# sensors_Layer_final.net
KiCad netlist of a schematic drawn in EAGLE
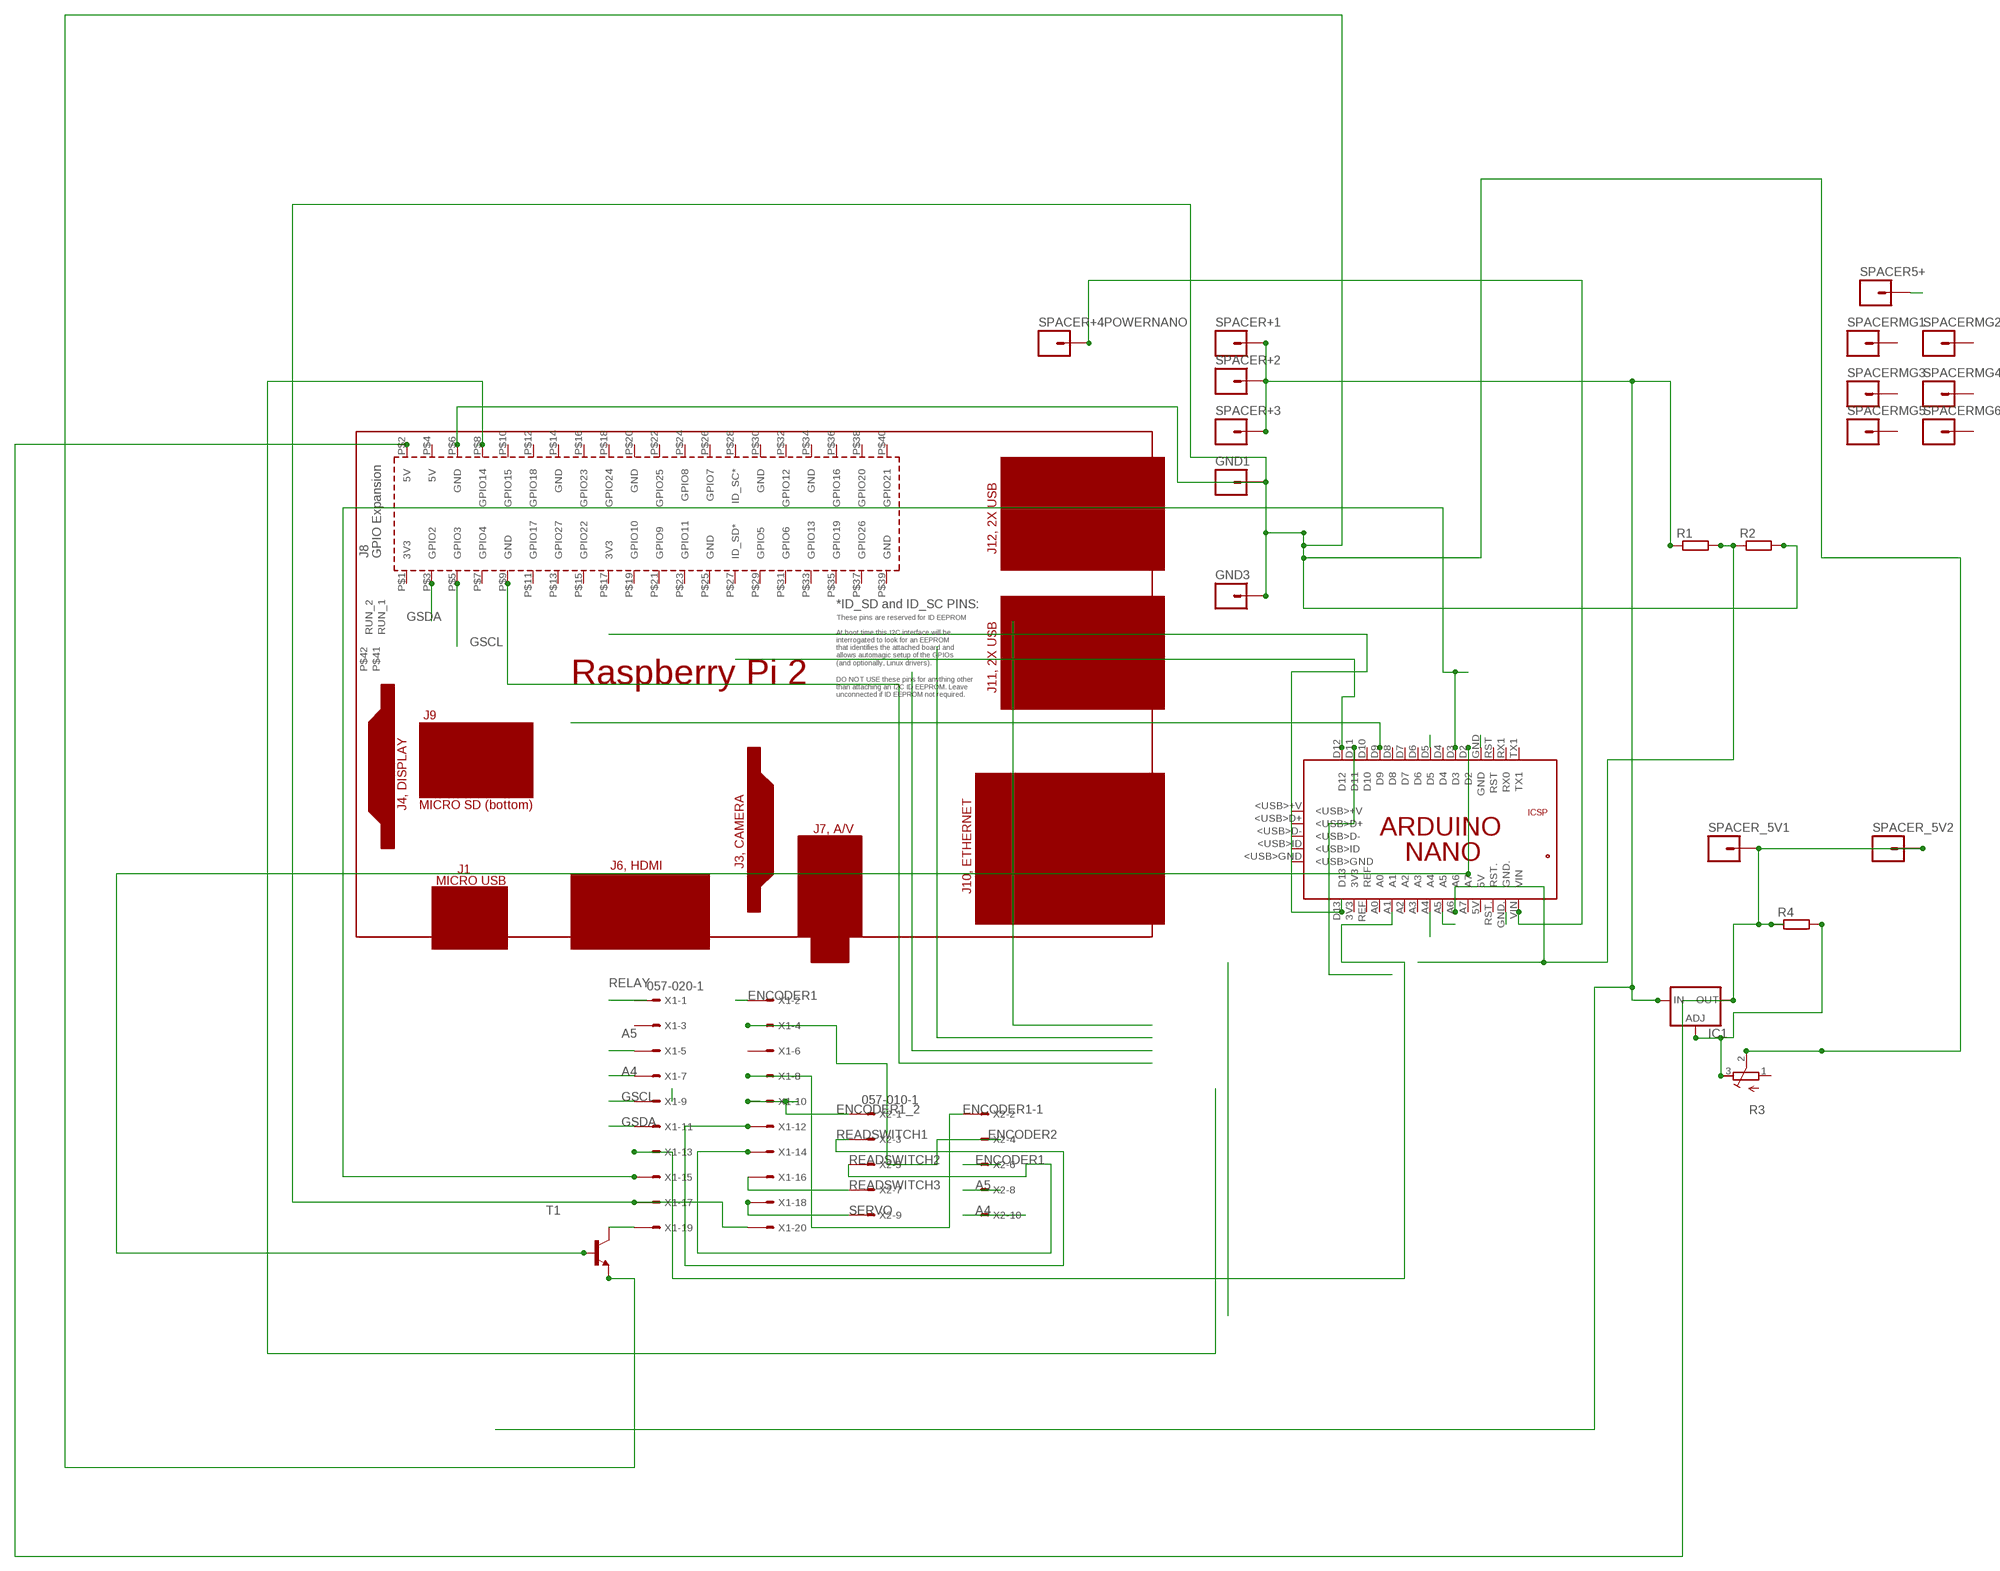
[diagram p0: schematic, sheet 1]

(export (version "E")
  (design (tool "Eeschema 10.0.6"))
  (components
    (comp (ref "GND1")
      (value "M01PTH_2MM")
      (footprint "eagle-import:1X01_2MM")
      (libsource (lib "eagle-import") (part "M01PTH_2MM"))
    )
    (comp (ref "GND3")
      (value "M01PTH_2MM")
      (footprint "eagle-import:1X01_2MM")
      (libsource (lib "eagle-import") (part "M01PTH_2MM"))
    )
    (comp (ref "IC1")
      (value "LM138-TO3")
      (footprint "eagle-import:TO3-K02")
      (libsource (lib "eagle-import") (part "LM138-TO3"))
    )
    (comp (ref "PCB1")
      (value "RPI2")
      (footprint "eagle-import:RPI2")
      (libsource (lib "eagle-import") (part "RPI2"))
    )
    (comp (ref "PCB2")
      (value "ARDUINO_NANO")
      (footprint "eagle-import:ARDUINO_NANO")
      (libsource (lib "eagle-import") (part "ARDUINO_NANO"))
    )
    (comp (ref "R1")
      (value "R-EU_0207/10")
      (footprint "eagle-import:0207_10")
      (libsource (lib "eagle-import") (part "R-EU_0207/10"))
    )
    (comp (ref "R2")
      (value "R-EU_0207/10")
      (footprint "eagle-import:0207_10")
      (libsource (lib "eagle-import") (part "R-EU_0207/10"))
    )
    (comp (ref "R3")
      (value "R-TRIMM64W")
      (footprint "eagle-import:RTRIM64W")
      (libsource (lib "eagle-import") (part "R-TRIMM64W"))
    )
    (comp (ref "R4")
      (value "R-EU_0207/10")
      (footprint "eagle-import:0207_10")
      (libsource (lib "eagle-import") (part "R-EU_0207/10"))
    )
    (comp (ref "SPACER+1")
      (value "M01PTH_2MM")
      (footprint "eagle-import:1X01_2MM")
      (libsource (lib "eagle-import") (part "M01PTH_2MM"))
    )
    (comp (ref "SPACER+2")
      (value "M01PTH_2MM")
      (footprint "eagle-import:1X01_2MM")
      (libsource (lib "eagle-import") (part "M01PTH_2MM"))
    )
    (comp (ref "SPACER+3")
      (value "M01PTH_2MM")
      (footprint "eagle-import:1X01_2MM")
      (libsource (lib "eagle-import") (part "M01PTH_2MM"))
    )
    (comp (ref "SPACER+4POWERNANO")
      (value "M01PTH_2MM")
      (footprint "eagle-import:1X01_2MM")
      (libsource (lib "eagle-import") (part "M01PTH_2MM"))
    )
    (comp (ref "SPACER5+")
      (value "M01PTH_2MM")
      (footprint "eagle-import:1X01_2MM")
      (libsource (lib "eagle-import") (part "M01PTH_2MM"))
    )
    (comp (ref "SPACERMG1")
      (value "M01PTH_2MM")
      (footprint "eagle-import:1X01_2MM")
      (libsource (lib "eagle-import") (part "M01PTH_2MM"))
    )
    (comp (ref "SPACERMG2")
      (value "M01PTH_2MM")
      (footprint "eagle-import:1X01_2MM")
      (libsource (lib "eagle-import") (part "M01PTH_2MM"))
    )
    (comp (ref "SPACERMG3")
      (value "M01PTH_2MM")
      (footprint "eagle-import:1X01_2MM")
      (libsource (lib "eagle-import") (part "M01PTH_2MM"))
    )
    (comp (ref "SPACERMG4")
      (value "M01PTH_2MM")
      (footprint "eagle-import:1X01_2MM")
      (libsource (lib "eagle-import") (part "M01PTH_2MM"))
    )
    (comp (ref "SPACERMG5")
      (value "M01PTH_2MM")
      (footprint "eagle-import:1X01_2MM")
      (libsource (lib "eagle-import") (part "M01PTH_2MM"))
    )
    (comp (ref "SPACERMG6")
      (value "M01PTH_2MM")
      (footprint "eagle-import:1X01_2MM")
      (libsource (lib "eagle-import") (part "M01PTH_2MM"))
    )
    (comp (ref "SPACER_5V1")
      (value "M01PTH_2MM")
      (footprint "eagle-import:1X01_2MM")
      (libsource (lib "eagle-import") (part "M01PTH_2MM"))
    )
    (comp (ref "SPACER_5V2")
      (value "M01PTH_2MM")
      (footprint "eagle-import:1X01_2MM")
      (libsource (lib "eagle-import") (part "M01PTH_2MM"))
    )
    (comp (ref "T1")
      (value "BC547-NPN-TO92-CBE")
      (footprint "eagle-import:TO92-CBE")
      (libsource (lib "eagle-import") (part "-NPN-TO92-CBEBC547"))
    )
    (comp (ref "X1")
      (value "057-020-1")
      (footprint "eagle-import:057-020-1")
      (libsource (lib "eagle-import") (part "057-020-1"))
    )
    (comp (ref "X2")
      (value "057-010-1")
      (footprint "eagle-import:057-010-1")
      (libsource (lib "eagle-import") (part "057-010-1"))
    )
  )
  (nets
    (net (code "1") (name "/5V") (class "Default")
      (node (ref "IC1") (pin "3") (pinfunction "OUT_3") (pintype "passive"))
      (node (ref "PCB1") (pin "P$2") (pinfunction "5V_P$2") (pintype "bidirectional"))
      (node (ref "R4") (pin "1") (pinfunction "1_1") (pintype "passive"))
      (node (ref "SPACER5+") (pin "1") (pinfunction "1_1") (pintype "passive"))
      (node (ref "SPACER_5V1") (pin "1") (pinfunction "1_1") (pintype "passive"))
      (node (ref "SPACER_5V2") (pin "1") (pinfunction "1_1") (pintype "passive"))
    )
    (net (code "2") (name "/A4") (class "Default")
      (node (ref "PCB2") (pin "A4") (pinfunction "A4_A4") (pintype "bidirectional"))
      (node (ref "X1") (pin "7") (pinfunction "S_7") (pintype "passive"))
      (node (ref "X2") (pin "10") (pinfunction "S_10") (pintype "passive"))
    )
    (net (code "3") (name "/A5") (class "Default")
      (node (ref "PCB2") (pin "A5") (pinfunction "A5_A5") (pintype "bidirectional"))
      (node (ref "X1") (pin "5") (pinfunction "S_5") (pintype "passive"))
      (node (ref "X2") (pin "8") (pinfunction "S_8") (pintype "passive"))
    )
    (net (code "4") (name "/ENCODER1") (class "Default")
      (node (ref "X1") (pin "2") (pinfunction "S_2") (pintype "passive"))
      (node (ref "X2") (pin "6") (pinfunction "S_6") (pintype "passive"))
    )
    (net (code "5") (name "/ENCODER1-1") (class "Default")
      (node (ref "X1") (pin "8") (pinfunction "S_8") (pintype "passive"))
      (node (ref "X2") (pin "2") (pinfunction "S_2") (pintype "passive"))
    )
    (net (code "6") (name "/ENCODER1_2") (class "Default")
      (node (ref "X1") (pin "10") (pinfunction "S_10") (pintype "passive"))
      (node (ref "X2") (pin "1") (pinfunction "S_1") (pintype "passive"))
    )
    (net (code "7") (name "/ENCODER2") (class "Default")
      (node (ref "X1") (pin "4") (pinfunction "S_4") (pintype "passive"))
      (node (ref "X2") (pin "4") (pinfunction "S_4") (pintype "passive"))
    )
    (net (code "8") (name "/GND") (class "Default")
      (node (ref "GND1") (pin "1") (pinfunction "1_1") (pintype "passive"))
      (node (ref "GND3") (pin "1") (pinfunction "1_1") (pintype "passive"))
      (node (ref "PCB1") (pin "P$6") (pinfunction "GND_P$6") (pintype "bidirectional"))
      (node (ref "PCB2") (pin "GND") (pinfunction "GND_GND") (pintype "bidirectional"))
      (node (ref "PCB2") (pin "GND.") (pinfunction "GND._GND.") (pintype "bidirectional"))
      (node (ref "R2") (pin "2") (pinfunction "2_2") (pintype "passive"))
      (node (ref "R3") (pin "2") (pinfunction "S_2") (pintype "passive"))
      (node (ref "T1") (pin "E") (pinfunction "E_E") (pintype "passive"))
      (node (ref "X1") (pin "17") (pinfunction "S_17") (pintype "passive"))
      (node (ref "X1") (pin "20") (pinfunction "S_20") (pintype "passive"))
    )
    (net (code "9") (name "/GSCL") (class "Default")
      (node (ref "PCB1") (pin "P$5") (pinfunction "GPIO3_P$5") (pintype "bidirectional"))
      (node (ref "X1") (pin "9") (pinfunction "S_9") (pintype "passive"))
    )
    (net (code "10") (name "/GSDA") (class "Default")
      (node (ref "PCB1") (pin "P$3") (pinfunction "GPIO2_P$3") (pintype "bidirectional"))
      (node (ref "X1") (pin "11") (pinfunction "S_11") (pintype "passive"))
    )
    (net (code "11") (name "/READSWITCH1") (class "Default")
      (node (ref "X1") (pin "12") (pinfunction "S_12") (pintype "passive"))
      (node (ref "X2") (pin "3") (pinfunction "S_3") (pintype "passive"))
    )
    (net (code "12") (name "/READSWITCH2") (class "Default")
      (node (ref "X1") (pin "14") (pinfunction "S_14") (pintype "passive"))
      (node (ref "X2") (pin "5") (pinfunction "S_5") (pintype "passive"))
    )
    (net (code "13") (name "/READSWITCH3") (class "Default")
      (node (ref "X1") (pin "16") (pinfunction "S_16") (pintype "passive"))
      (node (ref "X2") (pin "7") (pinfunction "S_7") (pintype "passive"))
    )
    (net (code "14") (name "/RELAY") (class "Default")
      (node (ref "PCB2") (pin "D5") (pinfunction "D5_D5") (pintype "bidirectional"))
      (node (ref "X1") (pin "1") (pinfunction "S_1") (pintype "passive"))
    )
    (net (code "15") (name "/SERVO") (class "Default")
      (node (ref "X1") (pin "18") (pinfunction "S_18") (pintype "passive"))
      (node (ref "X2") (pin "9") (pinfunction "S_9") (pintype "passive"))
    )
    (net (code "16") (name "Net-(IC1-ADJ)") (class "Default")
      (node (ref "IC1") (pin "2") (pinfunction "ADJ_2") (pintype "input"))
      (node (ref "R3") (pin "3") (pinfunction "A_3") (pintype "passive"))
      (node (ref "R4") (pin "2") (pinfunction "2_2") (pintype "passive"))
    )
    (net (code "17") (name "Net-(IC1-IN)") (class "Default")
      (node (ref "IC1") (pin "1") (pinfunction "IN_1") (pintype "input"))
      (node (ref "R1") (pin "1") (pinfunction "1_1") (pintype "passive"))
      (node (ref "SPACER+1") (pin "1") (pinfunction "1_1") (pintype "passive"))
      (node (ref "SPACER+2") (pin "1") (pinfunction "1_1") (pintype "passive"))
      (node (ref "SPACER+3") (pin "1") (pinfunction "1_1") (pintype "passive"))
    )
    (net (code "18") (name "Net-(PCB2-PadA6)") (class "Default")
      (node (ref "PCB2") (pin "A6") (pinfunction "A6_A6") (pintype "bidirectional"))
      (node (ref "R1") (pin "2") (pinfunction "2_2") (pintype "passive"))
      (node (ref "R2") (pin "1") (pinfunction "1_1") (pintype "passive"))
    )
    (net (code "19") (name "Net-(PCB2-PadD2)") (class "Default")
      (node (ref "PCB2") (pin "D2") (pinfunction "D2_D2") (pintype "bidirectional"))
      (node (ref "T1") (pin "B") (pinfunction "B_B") (pintype "passive"))
    )
    (net (code "20") (name "Net-(PCB2-PadVIN)") (class "Default")
      (node (ref "PCB2") (pin "VIN") (pinfunction "VIN_VIN") (pintype "bidirectional"))
      (node (ref "SPACER+4POWERNANO") (pin "1") (pinfunction "1_1") (pintype "passive"))
    )
    (net (code "21") (name "Net-(X1E-S)") (class "Default")
      (node (ref "PCB2") (pin "A1") (pinfunction "A1_A1") (pintype "bidirectional"))
      (node (ref "X1") (pin "13") (pinfunction "S_13") (pintype "passive"))
    )
    (net (code "22") (name "Net-(X1G-S)") (class "Default")
      (node (ref "PCB2") (pin "D3") (pinfunction "D3_D3") (pintype "bidirectional"))
      (node (ref "X1") (pin "15") (pinfunction "S_15") (pintype "passive"))
    )
    (net (code "23") (name "Net-(X1K-S)") (class "Default")
      (node (ref "T1") (pin "C") (pinfunction "C_C") (pintype "passive"))
      (node (ref "X1") (pin "19") (pinfunction "S_19") (pintype "passive"))
    )
    (net (code "24") (name "unconnected-(PCB1-3V3-PadP$1)") (class "Default")
      (node (ref "PCB1") (pin "P$1") (pinfunction "3V3_P$1") (pintype "bidirectional"))
    )
    (net (code "25") (name "unconnected-(PCB1-3V3-PadP$17)") (class "Default")
      (node (ref "PCB1") (pin "P$17") (pinfunction "3V3_P$17") (pintype "bidirectional"))
    )
    (net (code "26") (name "unconnected-(PCB1-5V-PadP$4)") (class "Default")
      (node (ref "PCB1") (pin "P$4") (pinfunction "5V_P$4") (pintype "bidirectional"))
    )
    (net (code "27") (name "unconnected-(PCB1-GND-PadP$9)") (class "Default")
      (node (ref "PCB1") (pin "P$9") (pinfunction "GND_P$9") (pintype "bidirectional"))
    )
    (net (code "28") (name "unconnected-(PCB1-GND-PadP$14)") (class "Default")
      (node (ref "PCB1") (pin "P$14") (pinfunction "GND_P$14") (pintype "bidirectional"))
    )
    (net (code "29") (name "unconnected-(PCB1-GND-PadP$20)") (class "Default")
      (node (ref "PCB1") (pin "P$20") (pinfunction "GND_P$20") (pintype "bidirectional"))
    )
    (net (code "30") (name "unconnected-(PCB1-GND-PadP$25)") (class "Default")
      (node (ref "PCB1") (pin "P$25") (pinfunction "GND_P$25") (pintype "bidirectional"))
    )
    (net (code "31") (name "unconnected-(PCB1-GND-PadP$30)") (class "Default")
      (node (ref "PCB1") (pin "P$30") (pinfunction "GND_P$30") (pintype "bidirectional"))
    )
    (net (code "32") (name "unconnected-(PCB1-GND-PadP$34)") (class "Default")
      (node (ref "PCB1") (pin "P$34") (pinfunction "GND_P$34") (pintype "bidirectional"))
    )
    (net (code "33") (name "unconnected-(PCB1-GND-PadP$39)") (class "Default")
      (node (ref "PCB1") (pin "P$39") (pinfunction "GND_P$39") (pintype "bidirectional"))
    )
    (net (code "34") (name "unconnected-(PCB1-GPIO4-PadP$7)") (class "Default")
      (node (ref "PCB1") (pin "P$7") (pinfunction "GPIO4_P$7") (pintype "bidirectional"))
    )
    (net (code "35") (name "unconnected-(PCB1-GPIO5-PadP$29)") (class "Default")
      (node (ref "PCB1") (pin "P$29") (pinfunction "GPIO5_P$29") (pintype "bidirectional"))
    )
    (net (code "36") (name "unconnected-(PCB1-GPIO6-PadP$31)") (class "Default")
      (node (ref "PCB1") (pin "P$31") (pinfunction "GPIO6_P$31") (pintype "bidirectional"))
    )
    (net (code "37") (name "unconnected-(PCB1-GPIO7-PadP$26)") (class "Default")
      (node (ref "PCB1") (pin "P$26") (pinfunction "GPIO7_P$26") (pintype "bidirectional"))
    )
    (net (code "38") (name "unconnected-(PCB1-GPIO8-PadP$24)") (class "Default")
      (node (ref "PCB1") (pin "P$24") (pinfunction "GPIO8_P$24") (pintype "bidirectional"))
    )
    (net (code "39") (name "unconnected-(PCB1-GPIO9-PadP$21)") (class "Default")
      (node (ref "PCB1") (pin "P$21") (pinfunction "GPIO9_P$21") (pintype "bidirectional"))
    )
    (net (code "40") (name "unconnected-(PCB1-GPIO10-PadP$19)") (class "Default")
      (node (ref "PCB1") (pin "P$19") (pinfunction "GPIO10_P$19") (pintype "bidirectional"))
    )
    (net (code "41") (name "unconnected-(PCB1-GPIO11-PadP$23)") (class "Default")
      (node (ref "PCB1") (pin "P$23") (pinfunction "GPIO11_P$23") (pintype "bidirectional"))
    )
    (net (code "42") (name "unconnected-(PCB1-GPIO12-PadP$32)") (class "Default")
      (node (ref "PCB1") (pin "P$32") (pinfunction "GPIO12_P$32") (pintype "bidirectional"))
    )
    (net (code "43") (name "unconnected-(PCB1-GPIO13-PadP$33)") (class "Default")
      (node (ref "PCB1") (pin "P$33") (pinfunction "GPIO13_P$33") (pintype "bidirectional"))
    )
    (net (code "44") (name "unconnected-(PCB1-GPIO14-PadP$8)") (class "Default")
      (node (ref "PCB1") (pin "P$8") (pinfunction "GPIO14_P$8") (pintype "bidirectional"))
    )
    (net (code "45") (name "unconnected-(PCB1-GPIO15-PadP$10)") (class "Default")
      (node (ref "PCB1") (pin "P$10") (pinfunction "GPIO15_P$10") (pintype "bidirectional"))
    )
    (net (code "46") (name "unconnected-(PCB1-GPIO16-PadP$36)") (class "Default")
      (node (ref "PCB1") (pin "P$36") (pinfunction "GPIO16_P$36") (pintype "bidirectional"))
    )
    (net (code "47") (name "unconnected-(PCB1-GPIO17-PadP$11)") (class "Default")
      (node (ref "PCB1") (pin "P$11") (pinfunction "GPIO17_P$11") (pintype "bidirectional"))
    )
    (net (code "48") (name "unconnected-(PCB1-GPIO18-PadP$12)") (class "Default")
      (node (ref "PCB1") (pin "P$12") (pinfunction "GPIO18_P$12") (pintype "bidirectional"))
    )
    (net (code "49") (name "unconnected-(PCB1-GPIO19-PadP$35)") (class "Default")
      (node (ref "PCB1") (pin "P$35") (pinfunction "GPIO19_P$35") (pintype "bidirectional"))
    )
    (net (code "50") (name "unconnected-(PCB1-GPIO20-PadP$38)") (class "Default")
      (node (ref "PCB1") (pin "P$38") (pinfunction "GPIO20_P$38") (pintype "bidirectional"))
    )
    (net (code "51") (name "unconnected-(PCB1-GPIO21-PadP$40)") (class "Default")
      (node (ref "PCB1") (pin "P$40") (pinfunction "GPIO21_P$40") (pintype "bidirectional"))
    )
    (net (code "52") (name "unconnected-(PCB1-GPIO22-PadP$15)") (class "Default")
      (node (ref "PCB1") (pin "P$15") (pinfunction "GPIO22_P$15") (pintype "bidirectional"))
    )
    (net (code "53") (name "unconnected-(PCB1-GPIO23-PadP$16)") (class "Default")
      (node (ref "PCB1") (pin "P$16") (pinfunction "GPIO23_P$16") (pintype "bidirectional"))
    )
    (net (code "54") (name "unconnected-(PCB1-GPIO24-PadP$18)") (class "Default")
      (node (ref "PCB1") (pin "P$18") (pinfunction "GPIO24_P$18") (pintype "bidirectional"))
    )
    (net (code "55") (name "unconnected-(PCB1-GPIO25-PadP$22)") (class "Default")
      (node (ref "PCB1") (pin "P$22") (pinfunction "GPIO25_P$22") (pintype "bidirectional"))
    )
    (net (code "56") (name "unconnected-(PCB1-GPIO26-PadP$37)") (class "Default")
      (node (ref "PCB1") (pin "P$37") (pinfunction "GPIO26_P$37") (pintype "bidirectional"))
    )
    (net (code "57") (name "unconnected-(PCB1-GPIO27-PadP$13)") (class "Default")
      (node (ref "PCB1") (pin "P$13") (pinfunction "GPIO27_P$13") (pintype "bidirectional"))
    )
    (net (code "58") (name "unconnected-(PCB1-ID_SC*-PadP$28)") (class "Default")
      (node (ref "PCB1") (pin "P$28") (pinfunction "ID_SC*_P$28") (pintype "bidirectional"))
    )
    (net (code "59") (name "unconnected-(PCB1-ID_SD*-PadP$27)") (class "Default")
      (node (ref "PCB1") (pin "P$27") (pinfunction "ID_SD*_P$27") (pintype "bidirectional"))
    )
    (net (code "60") (name "unconnected-(PCB1-RUN_1-PadP$41)") (class "Default")
      (node (ref "PCB1") (pin "P$41") (pinfunction "RUN_1_P$41") (pintype "bidirectional"))
    )
    (net (code "61") (name "unconnected-(PCB1-RUN_2-PadP$42)") (class "Default")
      (node (ref "PCB1") (pin "P$42") (pinfunction "RUN_2_P$42") (pintype "bidirectional"))
    )
    (net (code "62") (name "unconnected-(PCB2-Pad3V3)") (class "Default")
      (node (ref "PCB2") (pin "3V3") (pinfunction "3V3_3V3") (pintype "bidirectional"))
    )
    (net (code "63") (name "unconnected-(PCB2-Pad5V)") (class "Default")
      (node (ref "PCB2") (pin "5V") (pinfunction "5V_5V") (pintype "bidirectional"))
    )
    (net (code "64") (name "unconnected-(PCB2-Pad5V.)") (class "Default")
      (node (ref "PCB2") (pin "5V.") (pinfunction "5V._5V.") (pintype "bidirectional"))
    )
    (net (code "65") (name "unconnected-(PCB2-Pad<USB>+V)") (class "Default")
      (node (ref "PCB2") (pin "<USB>+V") (pinfunction "<USB>+V_<USB>+V") (pintype "bidirectional"))
    )
    (net (code "66") (name "unconnected-(PCB2-Pad<USB>D+)") (class "Default")
      (node (ref "PCB2") (pin "<USB>D+") (pinfunction "<USB>D+_<USB>D+") (pintype "bidirectional"))
    )
    (net (code "67") (name "unconnected-(PCB2-Pad<USB>D-)") (class "Default")
      (node (ref "PCB2") (pin "<USB>D-") (pinfunction "<USB>D-_<USB>D-") (pintype "bidirectional"))
    )
    (net (code "68") (name "unconnected-(PCB2-Pad<USB>GND)") (class "Default")
      (node (ref "PCB2") (pin "<USB>GND") (pinfunction "<USB>GND_<USB>GND") (pintype "bidirectional"))
    )
    (net (code "69") (name "unconnected-(PCB2-Pad<USB>ID)") (class "Default")
      (node (ref "PCB2") (pin "<USB>ID") (pinfunction "<USB>ID_<USB>ID") (pintype "bidirectional"))
    )
    (net (code "70") (name "unconnected-(PCB2-PadA0)") (class "Default")
      (node (ref "PCB2") (pin "A0") (pinfunction "A0_A0") (pintype "bidirectional"))
    )
    (net (code "71") (name "unconnected-(PCB2-PadA2)") (class "Default")
      (node (ref "PCB2") (pin "A2") (pinfunction "A2_A2") (pintype "bidirectional"))
    )
    (net (code "72") (name "unconnected-(PCB2-PadA3)") (class "Default")
      (node (ref "PCB2") (pin "A3") (pinfunction "A3_A3") (pintype "bidirectional"))
    )
    (net (code "73") (name "unconnected-(PCB2-PadA7)") (class "Default")
      (node (ref "PCB2") (pin "A7") (pinfunction "A7_A7") (pintype "bidirectional"))
    )
    (net (code "74") (name "unconnected-(PCB2-PadD4)") (class "Default")
      (node (ref "PCB2") (pin "D4") (pinfunction "D4_D4") (pintype "bidirectional"))
    )
    (net (code "75") (name "unconnected-(PCB2-PadD6)") (class "Default")
      (node (ref "PCB2") (pin "D6") (pinfunction "D6_D6") (pintype "bidirectional"))
    )
    (net (code "76") (name "unconnected-(PCB2-PadD7)") (class "Default")
      (node (ref "PCB2") (pin "D7") (pinfunction "D7_D7") (pintype "bidirectional"))
    )
    (net (code "77") (name "unconnected-(PCB2-PadD8)") (class "Default")
      (node (ref "PCB2") (pin "D8") (pinfunction "D8_D8") (pintype "bidirectional"))
    )
    (net (code "78") (name "unconnected-(PCB2-PadD9)") (class "Default")
      (node (ref "PCB2") (pin "D9") (pinfunction "D9_D9") (pintype "bidirectional"))
    )
    (net (code "79") (name "unconnected-(PCB2-PadD10)") (class "Default")
      (node (ref "PCB2") (pin "D10") (pinfunction "D10_D10") (pintype "bidirectional"))
    )
    (net (code "80") (name "unconnected-(PCB2-PadD11)") (class "Default")
      (node (ref "PCB2") (pin "D11") (pinfunction "D11_D11") (pintype "bidirectional"))
    )
    (net (code "81") (name "unconnected-(PCB2-PadD12)") (class "Default")
      (node (ref "PCB2") (pin "D12") (pinfunction "D12_D12") (pintype "bidirectional"))
    )
    (net (code "82") (name "unconnected-(PCB2-PadD13)") (class "Default")
      (node (ref "PCB2") (pin "D13") (pinfunction "D13_D13") (pintype "bidirectional"))
    )
    (net (code "83") (name "unconnected-(PCB2-PadGND_)") (class "Default")
      (node (ref "PCB2") (pin "GND_") (pinfunction "GND__GND_") (pintype "bidirectional"))
    )
    (net (code "84") (name "unconnected-(PCB2-PadMISO)") (class "Default")
      (node (ref "PCB2") (pin "MISO") (pinfunction "MISO_MISO") (pintype "bidirectional"))
    )
    (net (code "85") (name "unconnected-(PCB2-PadMOSI)") (class "Default")
      (node (ref "PCB2") (pin "MOSI") (pinfunction "MOSI_MOSI") (pintype "bidirectional"))
    )
    (net (code "86") (name "unconnected-(PCB2-PadREF)") (class "Default")
      (node (ref "PCB2") (pin "REF") (pinfunction "REF_REF") (pintype "bidirectional"))
    )
    (net (code "87") (name "unconnected-(PCB2-PadRESET..)") (class "Default")
      (node (ref "PCB2") (pin "RESET..") (pinfunction "RESET.._RESET..") (pintype "bidirectional"))
    )
    (net (code "88") (name "unconnected-(PCB2-PadRST)") (class "Default")
      (node (ref "PCB2") (pin "RST") (pinfunction "RST_RST") (pintype "bidirectional"))
    )
    (net (code "89") (name "unconnected-(PCB2-PadRST.)") (class "Default")
      (node (ref "PCB2") (pin "RST.") (pinfunction "RST._RST.") (pintype "bidirectional"))
    )
    (net (code "90") (name "unconnected-(PCB2-PadSCK)") (class "Default")
      (node (ref "PCB2") (pin "SCK") (pinfunction "SCK_SCK") (pintype "bidirectional"))
    )
    (net (code "91") (name "unconnected-(PCB2-PadTX1)") (class "Default")
      (node (ref "PCB2") (pin "TX1") (pinfunction "TX1_TX1") (pintype "bidirectional"))
    )
    (net (code "92") (name "unconnected-(PCB2-RX0-PadRX1)") (class "Default")
      (node (ref "PCB2") (pin "RX1") (pinfunction "RX0_RX1") (pintype "bidirectional"))
    )
    (net (code "93") (name "unconnected-(R3-E-Pad1)") (class "Default")
      (node (ref "R3") (pin "1") (pinfunction "E_1") (pintype "passive"))
    )
    (net (code "94") (name "unconnected-(SPACERMG1-Pad1)") (class "Default")
      (node (ref "SPACERMG1") (pin "1") (pinfunction "1_1") (pintype "passive"))
    )
    (net (code "95") (name "unconnected-(SPACERMG2-Pad1)") (class "Default")
      (node (ref "SPACERMG2") (pin "1") (pinfunction "1_1") (pintype "passive"))
    )
    (net (code "96") (name "unconnected-(SPACERMG3-Pad1)") (class "Default")
      (node (ref "SPACERMG3") (pin "1") (pinfunction "1_1") (pintype "passive"))
    )
    (net (code "97") (name "unconnected-(SPACERMG4-Pad1)") (class "Default")
      (node (ref "SPACERMG4") (pin "1") (pinfunction "1_1") (pintype "passive"))
    )
    (net (code "98") (name "unconnected-(SPACERMG5-Pad1)") (class "Default")
      (node (ref "SPACERMG5") (pin "1") (pinfunction "1_1") (pintype "passive"))
    )
    (net (code "99") (name "unconnected-(SPACERMG6-Pad1)") (class "Default")
      (node (ref "SPACERMG6") (pin "1") (pinfunction "1_1") (pintype "passive"))
    )
    (net (code "100") (name "unconnected-(X1N-S-Pad3)") (class "Default")
      (node (ref "X1") (pin "3") (pinfunction "S_3") (pintype "passive"))
    )
    (net (code "101") (name "unconnected-(X1Q-S-Pad6)") (class "Default")
      (node (ref "X1") (pin "6") (pinfunction "S_6") (pintype "passive"))
    )
  )
)
